# MainBoard_V100_PSU.net
KiCad netlist of a schematic drawn in Altium Designer
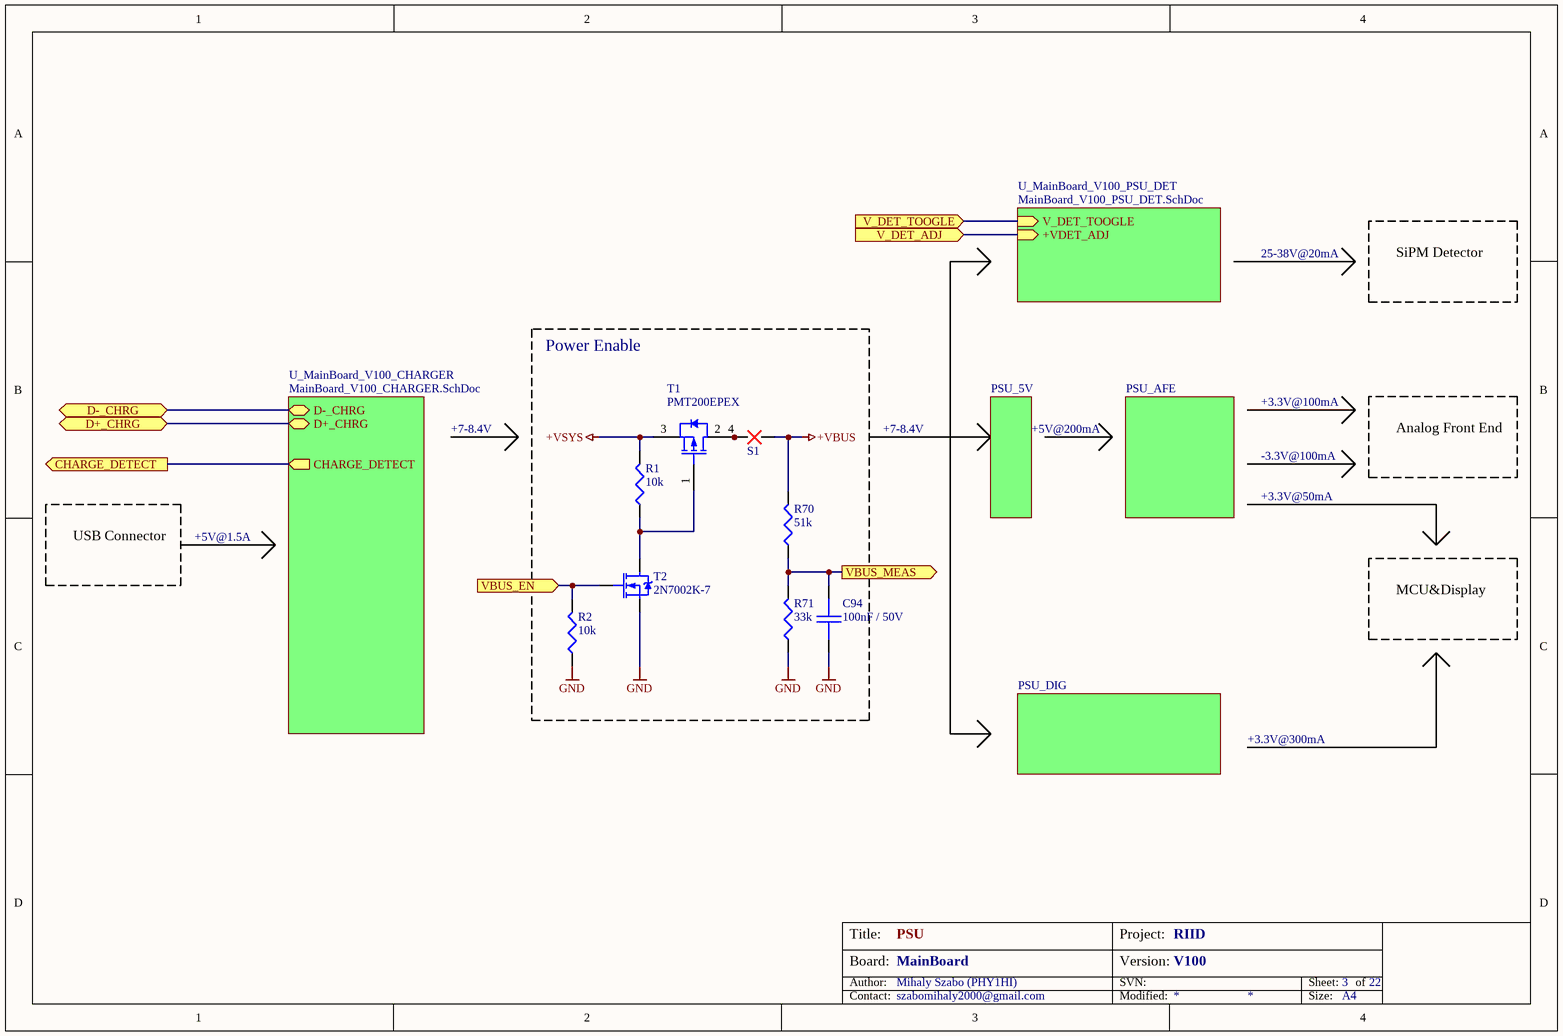
[diagram p0: MainBoard_V100_PSU.SchDoc]

(export (version "E")
  (design (tool "Eeschema 10.0.6"))
  (components
    (comp (ref "C94")
      (value "100nF / 50V")
      (footprint "0805_C")
      (description "100nF 50V X7R")
      (fields (field (name "PART NUMBER") "SMD0805-100nF-50V"))
      (libsource (lib "ALTIUM_DB_LIB") (part "CAP_NONPOL"))
    )
    (comp (ref "R1")
      (value "10k")
      (footprint "0805")
      (description "10k 0805 0.125W 1%")
      (fields (field (name "PART NUMBER") "SMD0805-10k 1%"))
      (libsource (lib "ALTIUM_DB_LIB") (part "RESISTOR"))
    )
    (comp (ref "R2")
      (value "10k")
      (footprint "0805")
      (description "10k 0805 0.125W 1%")
      (fields (field (name "PART NUMBER") "SMD0805-10k 1%"))
      (libsource (lib "ALTIUM_DB_LIB") (part "RESISTOR"))
    )
    (comp (ref "R70")
      (value "51k")
      (footprint "0805")
      (description "51k 0805 0.125W 5%")
      (fields (field (name "PART NUMBER") "SMD0805-51k 5%"))
      (libsource (lib "ALTIUM_DB_LIB") (part "RESISTOR"))
    )
    (comp (ref "R71")
      (value "33k")
      (footprint "0805")
      (description "33k 0805 0.125W 5%")
      (fields (field (name "PART NUMBER") "SMD0805-33k 5%"))
      (libsource (lib "ALTIUM_DB_LIB") (part "RESISTOR"))
    )
    (comp (ref "S1")
      (value "SPLITER")
      (footprint "SPLITER2_30mil_9mil")
      (description "SPLITER2_30mil_9mil")
      (libsource (lib "ALTIUM_DB_LIB") (part "SPLITER"))
    )
    (comp (ref "T1")
      (value "PMT200EPEX")
      (footprint "SOT-223")
      (description "PMT200EPEX Power MOSFET, P Channel, 70 V, 2.4 A, 0.167 ohm, SOT-223, Surface Mount")
      (libsource (lib "ALTIUM_DB_LIB") (part "MOSFET_P_CH_SOT223"))
    )
    (comp (ref "T2")
      (value "2N7002K-7")
      (footprint "SOT-23")
      (description "2N7002K-7 Power MOSFET, N Channel, 60 V, 300 mA, 2 ohm, SOT-23, Surface Mount")
      (libsource (lib "ALTIUM_DB_LIB") (part "MOSFET_N_CH"))
    )
  )
  (nets
    (net (code "1") (name "+VBUS") (class "Default")
      (node (ref "R70") (pin "2") (pintype "passive"))
      (node (ref "S1") (pin "2") (pinfunction "2_2") (pintype "passive"))
    )
    (net (code "2") (name "+VSYS") (class "Default")
      (node (ref "R1") (pin "2") (pintype "passive"))
      (node (ref "T1") (pin "3") (pinfunction "SOURCE_3") (pintype "passive"))
    )
    (net (code "6") (name "/VBUS_EN") (class "Default")
      (node (ref "R2") (pin "2") (pintype "passive"))
      (node (ref "T2") (pin "1") (pinfunction "G_1") (pintype "passive"))
    )
    (net (code "7") (name "/VBUS_MEAS") (class "Default")
      (node (ref "C94") (pin "1") (pintype "passive"))
      (node (ref "R70") (pin "1") (pintype "passive"))
      (node (ref "R71") (pin "2") (pintype "passive"))
    )
    (net (code "10") (name "GND") (class "Default")
      (node (ref "C94") (pin "2") (pintype "passive"))
      (node (ref "R2") (pin "1") (pintype "passive"))
      (node (ref "R71") (pin "1") (pintype "passive"))
      (node (ref "T2") (pin "2") (pinfunction "S_2") (pintype "passive"))
    )
    (net (code "11") (name "Net-(S1-Pad1)") (class "Default")
      (node (ref "S1") (pin "1") (pinfunction "1_1") (pintype "passive"))
      (node (ref "T1") (pin "2") (pinfunction "DRAIN_2") (pintype "passive"))
      (node (ref "T1") (pin "4") (pinfunction "DRAIN_4") (pintype "passive"))
    )
    (net (code "12") (name "Net-(T1-GATE)") (class "Default")
      (node (ref "R1") (pin "1") (pintype "passive"))
      (node (ref "T1") (pin "1") (pinfunction "GATE_1") (pintype "passive"))
      (node (ref "T2") (pin "3") (pinfunction "D_3") (pintype "passive"))
    )
  )
)
